# Switch.net
KiCad netlist of a schematic drawn in Altium Designer
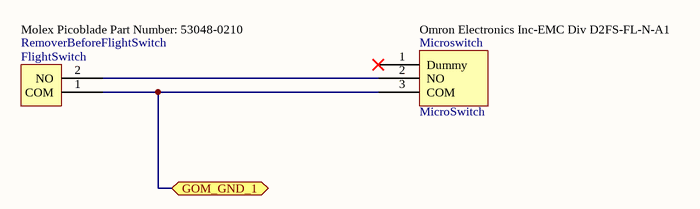
[diagram p0: Switch.SchDoc]

(export (version "E")
  (design (tool "Eeschema 10.0.6"))
  (components
    (comp (ref "FlightSwitch")
      (value "RemoverBeforeFlightSwitch")
      (footprint "UmbilicalConnectors:RemoverBeforeFlight Switch")
      (description "53048-0210 Molex Picoblade")
      (libsource (lib "UmbilicalBoardV2") (part "RemoverBeforeFlightSwitch"))
    )
    (comp (ref "Microswitch")
      (value "MicroSwitch")
      (footprint "UmbilicalConnectors:MicroSwitch_3pin")
      (description "Omron Electronics Inc-EMC Div D2FS-FL-N-A1")
      (libsource (lib "UmbilicalBoardV2") (part "MicroSwitch"))
    )
  )
  (nets
    (net (code "1") (name "/GOM_GND_1") (class "Default")
      (node (ref "FlightSwitch") (pin "1") (pinfunction "COM_1") (pintype "passive"))
      (node (ref "Microswitch") (pin "3") (pinfunction "COM_3") (pintype "passive"))
    )
    (net (code "2") (name "Net-(FlightSwitch-NO)") (class "Default")
      (node (ref "FlightSwitch") (pin "2") (pinfunction "NO_2") (pintype "passive"))
      (node (ref "Microswitch") (pin "2") (pinfunction "NO_2") (pintype "passive"))
    )
    (net (code "3") (name "unconnected-(Microswitch-Dummy-Pad1)") (class "Default")
      (node (ref "Microswitch") (pin "1") (pinfunction "Dummy_1") (pintype "passive+no_connect"))
    )
  )
)
